# Relay_Driver_Board_Tutorial.net
KiCad netlist of a schematic drawn in EAGLE
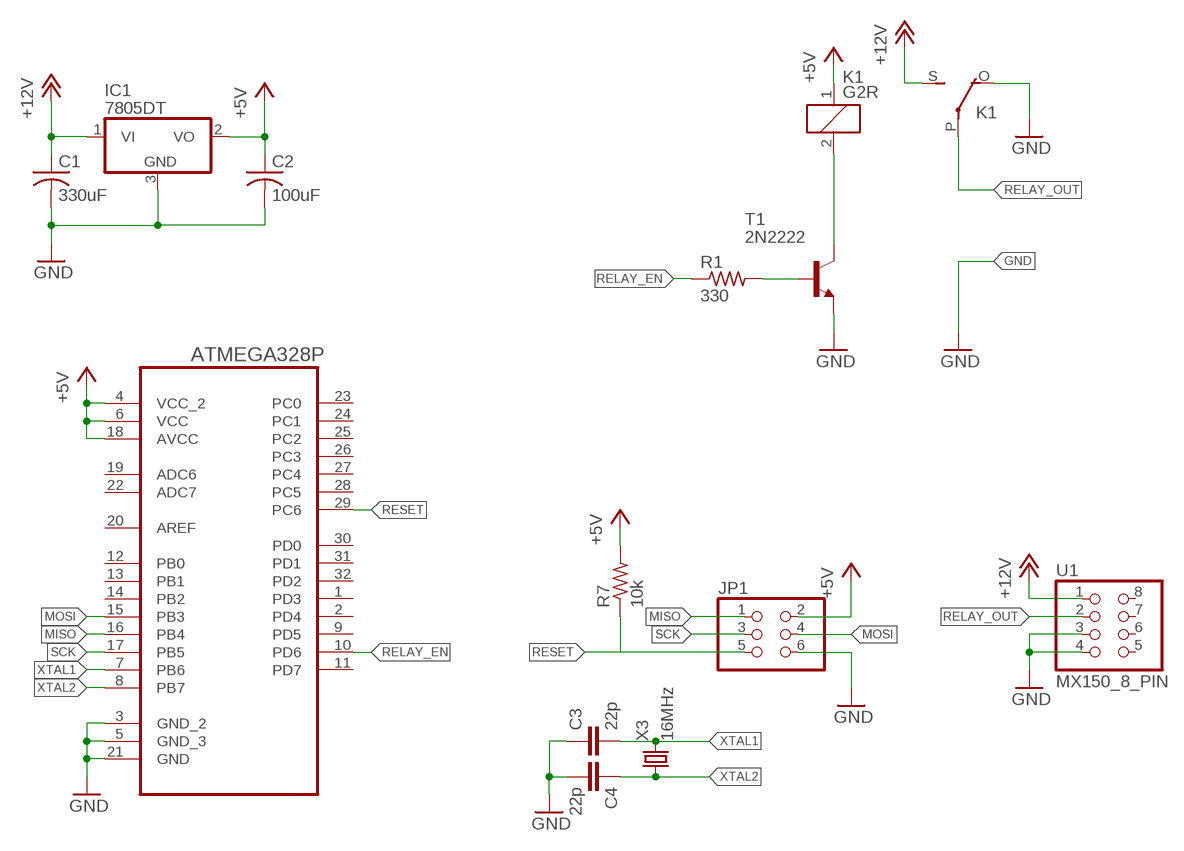
[diagram p0: schematic, sheet 1]

(export (version "E")
  (design (tool "Eeschema 10.0.6"))
  (components
    (comp (ref "ATMEGA328P")
      (value "ATMEGA328P-AU")
      (footprint "eagle-import:QFP80P900X900X120-32N")
      (libsource (lib "eagle-import") (part "ATMEGA328P-AU"))
    )
    (comp (ref "C1")
      (value "330uF")
      (footprint "eagle-import:C0805")
      (libsource (lib "eagle-import") (part "C-USC0805"))
    )
    (comp (ref "C2")
      (value "100uF")
      (footprint "eagle-import:C0805")
      (libsource (lib "eagle-import") (part "C-USC0805"))
    )
    (comp (ref "C3")
      (value "22p")
      (footprint "eagle-import:C0805K")
      (libsource (lib "eagle-import") (part "C-EUC0805K"))
    )
    (comp (ref "C4")
      (value "22p")
      (footprint "eagle-import:C0805K")
      (libsource (lib "eagle-import") (part "C-EUC0805K"))
    )
    (comp (ref "IC1")
      (value "7805DT")
      (footprint "eagle-import:TO252")
      (libsource (lib "eagle-import") (part "78DT05"))
    )
    (comp (ref "JP1")
      (value "PINHD-2X3")
      (footprint "eagle-import:2X03")
      (libsource (lib "eagle-import") (part "PINHD-2X3"))
    )
    (comp (ref "K1")
      (value "G2R")
      (footprint "eagle-import:G2R")
      (libsource (lib "eagle-import") (part "G2R"))
    )
    (comp (ref "R1")
      (value "330")
      (footprint "eagle-import:R0805")
      (libsource (lib "eagle-import") (part "R-US_R0805"))
    )
    (comp (ref "R7")
      (value "10k")
      (footprint "eagle-import:R0805")
      (libsource (lib "eagle-import") (part "R-US_R0805"))
    )
    (comp (ref "T1")
      (value "2N2222")
      (footprint "eagle-import:TO92")
      (libsource (lib "eagle-import") (part "2N3904"))
    )
    (comp (ref "U1")
      (value "MX150_8_PIN")
      (footprint "eagle-import:MX150_8")
      (libsource (lib "eagle-import") (part "MX150_8_PIN"))
    )
    (comp (ref "X3")
      (value "16MHz")
      (footprint "eagle-import:QS")
      (libsource (lib "eagle-import") (part "CRYSTAL"))
    )
  )
  (nets
    (net (code "1") (name "+5V") (class "Default")
      (node (ref "ATMEGA328P") (pin "18") (pinfunction "AVCC_18") (pintype "power_in"))
      (node (ref "ATMEGA328P") (pin "4") (pinfunction "VCC_2_4") (pintype "power_in"))
      (node (ref "ATMEGA328P") (pin "6") (pinfunction "VCC_6") (pintype "power_in"))
      (node (ref "C2") (pin "1") (pinfunction "1_1") (pintype "passive"))
      (node (ref "IC1") (pin "2") (pinfunction "VO_2") (pintype "passive"))
      (node (ref "JP1") (pin "2") (pinfunction "2_2") (pintype "passive"))
      (node (ref "K1") (pin "1") (pinfunction "1_1") (pintype "passive"))
      (node (ref "R7") (pin "2") (pinfunction "2_2") (pintype "passive"))
    )
    (net (code "2") (name "+12V") (class "Default")
      (node (ref "C1") (pin "1") (pinfunction "1_1") (pintype "passive"))
      (node (ref "IC1") (pin "1") (pinfunction "VI_1") (pintype "input"))
      (node (ref "K1") (pin "S") (pinfunction "S_S") (pintype "passive"))
      (node (ref "U1") (pin "1") (pinfunction "1_1") (pintype "passive"))
    )
    (net (code "3") (name "GND") (class "Default")
      (node (ref "ATMEGA328P") (pin "21") (pinfunction "GND_21") (pintype "passive"))
      (node (ref "ATMEGA328P") (pin "3") (pinfunction "GND_2_3") (pintype "passive"))
      (node (ref "ATMEGA328P") (pin "5") (pinfunction "GND_3_5") (pintype "passive"))
      (node (ref "C1") (pin "2") (pinfunction "2_2") (pintype "passive"))
      (node (ref "C2") (pin "2") (pinfunction "2_2") (pintype "passive"))
      (node (ref "C3") (pin "1") (pinfunction "1_1") (pintype "passive"))
      (node (ref "C4") (pin "2") (pinfunction "2_2") (pintype "passive"))
      (node (ref "IC1") (pin "3") (pinfunction "GND_3") (pintype "passive"))
      (node (ref "JP1") (pin "6") (pinfunction "6_6") (pintype "passive"))
      (node (ref "K1") (pin "O") (pinfunction "O_O") (pintype "passive"))
      (node (ref "T1") (pin "3") (pinfunction "E_3") (pintype "passive"))
      (node (ref "U1") (pin "3") (pinfunction "5_3") (pintype "passive"))
      (node (ref "U1") (pin "4") (pinfunction "7_4") (pintype "passive"))
    )
    (net (code "4") (name "MISO") (class "Default")
      (node (ref "ATMEGA328P") (pin "16") (pinfunction "PB4_16") (pintype "bidirectional"))
      (node (ref "JP1") (pin "1") (pinfunction "1_1") (pintype "passive"))
    )
    (net (code "5") (name "MOSI") (class "Default")
      (node (ref "ATMEGA328P") (pin "15") (pinfunction "PB3_15") (pintype "bidirectional"))
      (node (ref "JP1") (pin "4") (pinfunction "4_4") (pintype "passive"))
    )
    (net (code "6") (name "Net-(T1-B)") (class "Default")
      (node (ref "R1") (pin "2") (pinfunction "2_2") (pintype "passive"))
      (node (ref "T1") (pin "2") (pinfunction "B_2") (pintype "passive"))
    )
    (net (code "7") (name "Net-(T1-C)") (class "Default")
      (node (ref "K1") (pin "2") (pinfunction "2_2") (pintype "passive"))
      (node (ref "T1") (pin "1") (pinfunction "C_1") (pintype "passive"))
    )
    (net (code "8") (name "RELAY_EN") (class "Default")
      (node (ref "ATMEGA328P") (pin "10") (pinfunction "PD6_10") (pintype "bidirectional"))
      (node (ref "R1") (pin "1") (pinfunction "1_1") (pintype "passive"))
    )
    (net (code "9") (name "RELAY_OUT") (class "Default")
      (node (ref "K1") (pin "P") (pinfunction "P_P") (pintype "passive"))
      (node (ref "U1") (pin "2") (pinfunction "3_2") (pintype "passive"))
    )
    (net (code "10") (name "RESET") (class "Default")
      (node (ref "ATMEGA328P") (pin "29") (pinfunction "PC6_29") (pintype "bidirectional"))
      (node (ref "JP1") (pin "5") (pinfunction "5_5") (pintype "passive"))
      (node (ref "R7") (pin "1") (pinfunction "1_1") (pintype "passive"))
    )
    (net (code "11") (name "SCK") (class "Default")
      (node (ref "ATMEGA328P") (pin "17") (pinfunction "PB5_17") (pintype "bidirectional"))
      (node (ref "JP1") (pin "3") (pinfunction "3_3") (pintype "passive"))
    )
    (net (code "12") (name "XTAL1") (class "Default")
      (node (ref "ATMEGA328P") (pin "7") (pinfunction "PB6_7") (pintype "bidirectional"))
      (node (ref "C3") (pin "2") (pinfunction "2_2") (pintype "passive"))
      (node (ref "X3") (pin "2") (pinfunction "2_2") (pintype "passive"))
    )
    (net (code "13") (name "XTAL2") (class "Default")
      (node (ref "ATMEGA328P") (pin "8") (pinfunction "PB7_8") (pintype "bidirectional"))
      (node (ref "C4") (pin "1") (pinfunction "1_1") (pintype "passive"))
      (node (ref "X3") (pin "1") (pinfunction "1_1") (pintype "passive"))
    )
    (net (code "14") (name "unconnected-(ATMEGA328P-ADC6-Pad19)") (class "Default")
      (node (ref "ATMEGA328P") (pin "19") (pinfunction "ADC6_19") (pintype "input"))
    )
    (net (code "15") (name "unconnected-(ATMEGA328P-ADC7-Pad22)") (class "Default")
      (node (ref "ATMEGA328P") (pin "22") (pinfunction "ADC7_22") (pintype "input"))
    )
    (net (code "16") (name "unconnected-(ATMEGA328P-AREF-Pad20)") (class "Default")
      (node (ref "ATMEGA328P") (pin "20") (pinfunction "AREF_20") (pintype "input"))
    )
    (net (code "17") (name "unconnected-(ATMEGA328P-PB0-Pad12)") (class "Default")
      (node (ref "ATMEGA328P") (pin "12") (pinfunction "PB0_12") (pintype "bidirectional"))
    )
    (net (code "18") (name "unconnected-(ATMEGA328P-PB1-Pad13)") (class "Default")
      (node (ref "ATMEGA328P") (pin "13") (pinfunction "PB1_13") (pintype "bidirectional"))
    )
    (net (code "19") (name "unconnected-(ATMEGA328P-PB2-Pad14)") (class "Default")
      (node (ref "ATMEGA328P") (pin "14") (pinfunction "PB2_14") (pintype "bidirectional"))
    )
    (net (code "20") (name "unconnected-(ATMEGA328P-PC0-Pad23)") (class "Default")
      (node (ref "ATMEGA328P") (pin "23") (pinfunction "PC0_23") (pintype "bidirectional"))
    )
    (net (code "21") (name "unconnected-(ATMEGA328P-PC1-Pad24)") (class "Default")
      (node (ref "ATMEGA328P") (pin "24") (pinfunction "PC1_24") (pintype "bidirectional"))
    )
    (net (code "22") (name "unconnected-(ATMEGA328P-PC2-Pad25)") (class "Default")
      (node (ref "ATMEGA328P") (pin "25") (pinfunction "PC2_25") (pintype "bidirectional"))
    )
    (net (code "23") (name "unconnected-(ATMEGA328P-PC3-Pad26)") (class "Default")
      (node (ref "ATMEGA328P") (pin "26") (pinfunction "PC3_26") (pintype "bidirectional"))
    )
    (net (code "24") (name "unconnected-(ATMEGA328P-PC4-Pad27)") (class "Default")
      (node (ref "ATMEGA328P") (pin "27") (pinfunction "PC4_27") (pintype "bidirectional"))
    )
    (net (code "25") (name "unconnected-(ATMEGA328P-PC5-Pad28)") (class "Default")
      (node (ref "ATMEGA328P") (pin "28") (pinfunction "PC5_28") (pintype "bidirectional"))
    )
    (net (code "26") (name "unconnected-(ATMEGA328P-PD0-Pad30)") (class "Default")
      (node (ref "ATMEGA328P") (pin "30") (pinfunction "PD0_30") (pintype "bidirectional"))
    )
    (net (code "27") (name "unconnected-(ATMEGA328P-PD1-Pad31)") (class "Default")
      (node (ref "ATMEGA328P") (pin "31") (pinfunction "PD1_31") (pintype "bidirectional"))
    )
    (net (code "28") (name "unconnected-(ATMEGA328P-PD2-Pad32)") (class "Default")
      (node (ref "ATMEGA328P") (pin "32") (pinfunction "PD2_32") (pintype "bidirectional"))
    )
    (net (code "29") (name "unconnected-(ATMEGA328P-PD3-Pad1)") (class "Default")
      (node (ref "ATMEGA328P") (pin "1") (pinfunction "PD3_1") (pintype "bidirectional"))
    )
    (net (code "30") (name "unconnected-(ATMEGA328P-PD4-Pad2)") (class "Default")
      (node (ref "ATMEGA328P") (pin "2") (pinfunction "PD4_2") (pintype "bidirectional"))
    )
    (net (code "31") (name "unconnected-(ATMEGA328P-PD5-Pad9)") (class "Default")
      (node (ref "ATMEGA328P") (pin "9") (pinfunction "PD5_9") (pintype "bidirectional"))
    )
    (net (code "32") (name "unconnected-(ATMEGA328P-PD7-Pad11)") (class "Default")
      (node (ref "ATMEGA328P") (pin "11") (pinfunction "PD7_11") (pintype "bidirectional"))
    )
    (net (code "33") (name "unconnected-(U1-2-Pad8)") (class "Default")
      (node (ref "U1") (pin "8") (pinfunction "2_8") (pintype "passive"))
    )
    (net (code "34") (name "unconnected-(U1-4-Pad7)") (class "Default")
      (node (ref "U1") (pin "7") (pinfunction "4_7") (pintype "passive"))
    )
    (net (code "35") (name "unconnected-(U1-8-Pad5)") (class "Default")
      (node (ref "U1") (pin "5") (pinfunction "8_5") (pintype "passive"))
    )
    (net (code "36") (name "unconnected-(U1-Pad6)") (class "Default")
      (node (ref "U1") (pin "6") (pinfunction "6_6") (pintype "passive"))
    )
  )
)
